# 9V-Reg.net
KiCad netlist of a schematic drawn in EAGLE
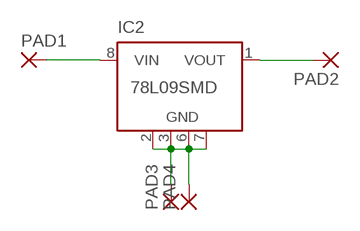
[diagram p0: schematic, sheet 1]

(export (version "E")
  (design (tool "Eeschema 10.0.6"))
  (components
    (comp (ref "IC2")
      (value "78L09SMD")
      (footprint "eagle-import:SO08")
      (libsource (lib "eagle-import") (part "78LSMD05"))
    )
    (comp (ref "PAD1")
      (value "SMD2")
      (footprint "eagle-import:SMD1,27-2,54")
      (libsource (lib "eagle-import") (part "SMD2"))
    )
    (comp (ref "PAD2")
      (value "SMD2")
      (footprint "eagle-import:SMD1,27-2,54")
      (libsource (lib "eagle-import") (part "SMD2"))
    )
    (comp (ref "PAD3")
      (value "SMD2")
      (footprint "eagle-import:SMD1,27-2,54")
      (libsource (lib "eagle-import") (part "SMD2"))
    )
    (comp (ref "PAD4")
      (value "SMD2")
      (footprint "eagle-import:SMD1,27-2,54")
      (libsource (lib "eagle-import") (part "SMD2"))
    )
  )
  (nets
    (net (code "1") (name "Net-(IC2A-VIN)") (class "Default")
      (node (ref "IC2") (pin "8") (pinfunction "VIN_8") (pintype "passive"))
      (node (ref "PAD1") (pin "1") (pinfunction "P_1") (pintype "passive"))
    )
    (net (code "2") (name "Net-(IC2A-VOUT)") (class "Default")
      (node (ref "IC2") (pin "1") (pinfunction "VOUT_1") (pintype "output"))
      (node (ref "PAD2") (pin "1") (pinfunction "P_1") (pintype "passive"))
    )
    (net (code "3") (name "Net-(PAD3-P)") (class "Default")
      (node (ref "IC2") (pin "2") (pinfunction "GND_2") (pintype "power_in"))
      (node (ref "IC2") (pin "3") (pinfunction "GND_3") (pintype "power_in"))
      (node (ref "IC2") (pin "6") (pinfunction "GND_6") (pintype "power_in"))
      (node (ref "IC2") (pin "7") (pinfunction "GND_7") (pintype "power_in"))
      (node (ref "PAD3") (pin "1") (pinfunction "P_1") (pintype "passive"))
      (node (ref "PAD4") (pin "1") (pinfunction "P_1") (pintype "passive"))
    )
  )
)
